# Programmer.net
KiCad netlist of a schematic drawn in EAGLE
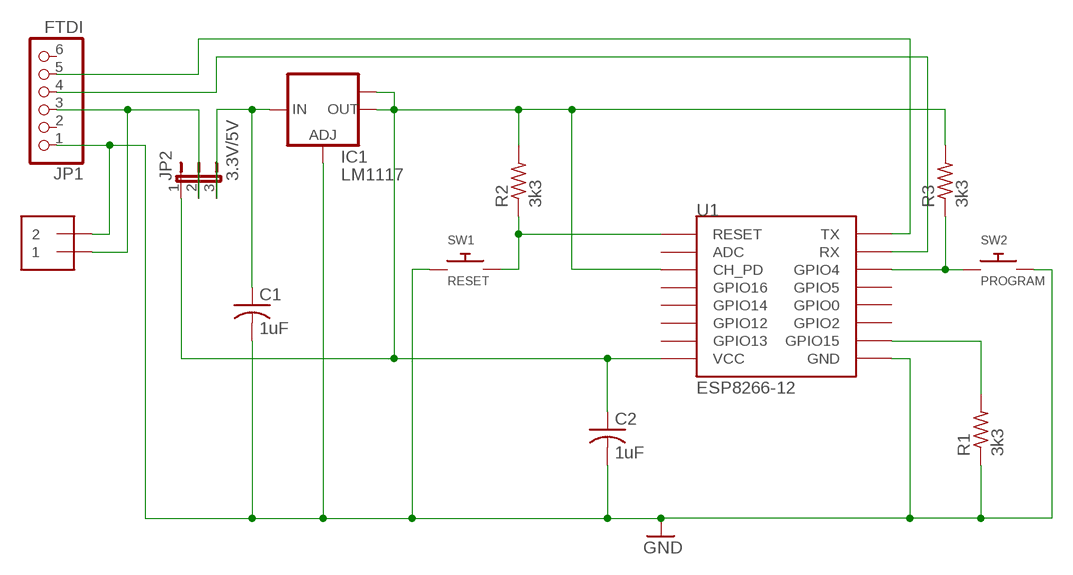
[diagram p0: schematic, sheet 1]

(export (version "E")
  (design (tool "Eeschema 10.0.6"))
  (components
    (comp (ref "C1")
      (value "1uF")
      (footprint "eagle-import:C0805")
      (libsource (lib "eagle-import") (part "C-USC0805"))
    )
    (comp (ref "C2")
      (value "1uF")
      (footprint "eagle-import:C0805")
      (libsource (lib "eagle-import") (part "C-USC0805"))
    )
    (comp (ref "IC1")
      (value "LM1117")
      (footprint "eagle-import:SOT223")
      (libsource (lib "eagle-import") (part "LM1117IMPX-ADJ"))
    )
    (comp (ref "J1")
      (value "1X2")
      (footprint "eagle-import:1X02")
      (libsource (lib "eagle-import") (part "1X2"))
    )
    (comp (ref "JP1")
      (value "FTDI")
      (footprint "eagle-import:1X06")
      (libsource (lib "eagle-import") (part "PINHD-1X6"))
    )
    (comp (ref "JP2")
      (value "3.3V/5V")
      (footprint "eagle-import:JP2")
      (libsource (lib "eagle-import") (part "JP2E"))
    )
    (comp (ref "R1")
      (value "3k3")
      (footprint "eagle-import:M0805")
      (libsource (lib "eagle-import") (part "R-US_M0805"))
    )
    (comp (ref "R2")
      (value "3k3")
      (footprint "eagle-import:M0805")
      (libsource (lib "eagle-import") (part "R-US_M0805"))
    )
    (comp (ref "R3")
      (value "3k3")
      (footprint "eagle-import:M0805")
      (libsource (lib "eagle-import") (part "R-US_M0805"))
    )
    (comp (ref "SW1")
      (value "RESET")
      (footprint "eagle-import:PUSHBUTTON_SMD_SJ")
      (libsource (lib "eagle-import") (part "SWITCH_PUSHBUTTONSOFTTOUCHSMD_SJ"))
    )
    (comp (ref "SW2")
      (value "PROGRAM")
      (footprint "eagle-import:PUSHBUTTON_SMD_SJ")
      (libsource (lib "eagle-import") (part "SWITCH_PUSHBUTTONSOFTTOUCHSMD_SJ"))
    )
    (comp (ref "U1")
      (value "ESP8266-12")
      (footprint "eagle-import:ESP12")
      (libsource (lib "eagle-import") (part "ESP12"))
    )
  )
  (nets
    (net (code "1") (name "GND") (class "Default")
      (node (ref "C1") (pin "2") (pinfunction "2_2") (pintype "passive"))
      (node (ref "C2") (pin "2") (pinfunction "2_2") (pintype "passive"))
      (node (ref "IC1") (pin "1") (pinfunction "ADJ_1") (pintype "input"))
      (node (ref "J1") (pin "2") (pinfunction "2_2") (pintype "passive"))
      (node (ref "JP1") (pin "1") (pinfunction "1_1") (pintype "passive"))
      (node (ref "R1") (pin "1") (pinfunction "1_1") (pintype "passive"))
      (node (ref "SW1") (pin "P$1") (pinfunction "P$1_P$1") (pintype "passive"))
      (node (ref "SW2") (pin "P$2") (pinfunction "P$2_P$2") (pintype "passive"))
      (node (ref "U1") (pin "GND") (pinfunction "GND_GND") (pintype "bidirectional"))
    )
    (net (code "2") (name "Net-(IC1-IN)") (class "Default")
      (node (ref "C1") (pin "1") (pinfunction "1_1") (pintype "passive"))
      (node (ref "IC1") (pin "3") (pinfunction "IN_3") (pintype "input"))
      (node (ref "JP2") (pin "3") (pinfunction "3_3") (pintype "passive"))
    )
    (net (code "3") (name "Net-(IC1-OUT)") (class "Default")
      (node (ref "C2") (pin "1") (pinfunction "1_1") (pintype "passive"))
      (node (ref "IC1") (pin "2") (pinfunction "OUT_2") (pintype "passive"))
      (node (ref "IC1") (pin "TAB") (pinfunction "OUT1_TAB") (pintype "passive"))
      (node (ref "JP2") (pin "1") (pinfunction "1_1") (pintype "passive"))
      (node (ref "R2") (pin "2") (pinfunction "2_2") (pintype "passive"))
      (node (ref "R3") (pin "2") (pinfunction "2_2") (pintype "passive"))
      (node (ref "U1") (pin "CH_PD") (pinfunction "CH_PD_CH_PD") (pintype "bidirectional"))
      (node (ref "U1") (pin "VCC") (pinfunction "VCC_VCC") (pintype "bidirectional"))
    )
    (net (code "4") (name "Net-(J1-Pad1)") (class "Default")
      (node (ref "J1") (pin "1") (pinfunction "1_1") (pintype "passive"))
      (node (ref "JP1") (pin "3") (pinfunction "3_3") (pintype "passive"))
      (node (ref "JP2") (pin "2") (pinfunction "2_2") (pintype "passive"))
    )
    (net (code "5") (name "Net-(JP1-Pad4)") (class "Default")
      (node (ref "JP1") (pin "4") (pinfunction "4_4") (pintype "passive"))
      (node (ref "U1") (pin "RX") (pinfunction "RX_RX") (pintype "bidirectional"))
    )
    (net (code "6") (name "Net-(JP1-Pad5)") (class "Default")
      (node (ref "JP1") (pin "5") (pinfunction "5_5") (pintype "passive"))
      (node (ref "U1") (pin "TX") (pinfunction "TX_TX") (pintype "bidirectional"))
    )
    (net (code "7") (name "Net-(R1-Pad2)") (class "Default")
      (node (ref "R1") (pin "2") (pinfunction "2_2") (pintype "passive"))
      (node (ref "U1") (pin "GPIO15") (pinfunction "GPIO15_GPIO15") (pintype "bidirectional"))
    )
    (net (code "8") (name "Net-(R2-Pad1)") (class "Default")
      (node (ref "R2") (pin "1") (pinfunction "1_1") (pintype "passive"))
      (node (ref "SW1") (pin "P$2") (pinfunction "P$2_P$2") (pintype "passive"))
      (node (ref "U1") (pin "RESET") (pinfunction "RESET_RESET") (pintype "bidirectional"))
    )
    (net (code "9") (name "Net-(R3-Pad1)") (class "Default")
      (node (ref "R3") (pin "1") (pinfunction "1_1") (pintype "passive"))
      (node (ref "SW2") (pin "P$1") (pinfunction "P$1_P$1") (pintype "passive"))
      (node (ref "U1") (pin "GPIO4") (pinfunction "GPIO4_GPIO4") (pintype "bidirectional"))
    )
    (net (code "10") (name "unconnected-(JP1-Pad2)") (class "Default")
      (node (ref "JP1") (pin "2") (pinfunction "2_2") (pintype "passive"))
    )
    (net (code "11") (name "unconnected-(JP1-Pad6)") (class "Default")
      (node (ref "JP1") (pin "6") (pinfunction "6_6") (pintype "passive"))
    )
    (net (code "12") (name "unconnected-(U1-PadADC)") (class "Default")
      (node (ref "U1") (pin "ADC") (pinfunction "ADC_ADC") (pintype "bidirectional"))
    )
    (net (code "13") (name "unconnected-(U1-PadGPIO0)") (class "Default")
      (node (ref "U1") (pin "GPIO0") (pinfunction "GPIO0_GPIO0") (pintype "bidirectional"))
    )
    (net (code "14") (name "unconnected-(U1-PadGPIO2)") (class "Default")
      (node (ref "U1") (pin "GPIO2") (pinfunction "GPIO2_GPIO2") (pintype "bidirectional"))
    )
    (net (code "15") (name "unconnected-(U1-PadGPIO5)") (class "Default")
      (node (ref "U1") (pin "GPIO5") (pinfunction "GPIO5_GPIO5") (pintype "bidirectional"))
    )
    (net (code "16") (name "unconnected-(U1-PadGPIO12)") (class "Default")
      (node (ref "U1") (pin "GPIO12") (pinfunction "GPIO12_GPIO12") (pintype "bidirectional"))
    )
    (net (code "17") (name "unconnected-(U1-PadGPIO13)") (class "Default")
      (node (ref "U1") (pin "GPIO13") (pinfunction "GPIO13_GPIO13") (pintype "bidirectional"))
    )
    (net (code "18") (name "unconnected-(U1-PadGPIO14)") (class "Default")
      (node (ref "U1") (pin "GPIO14") (pinfunction "GPIO14_GPIO14") (pintype "bidirectional"))
    )
    (net (code "19") (name "unconnected-(U1-PadGPIO16)") (class "Default")
      (node (ref "U1") (pin "GPIO16") (pinfunction "GPIO16_GPIO16") (pintype "bidirectional"))
    )
  )
)
